# 1020.net
KiCad netlist of a schematic drawn in EAGLE
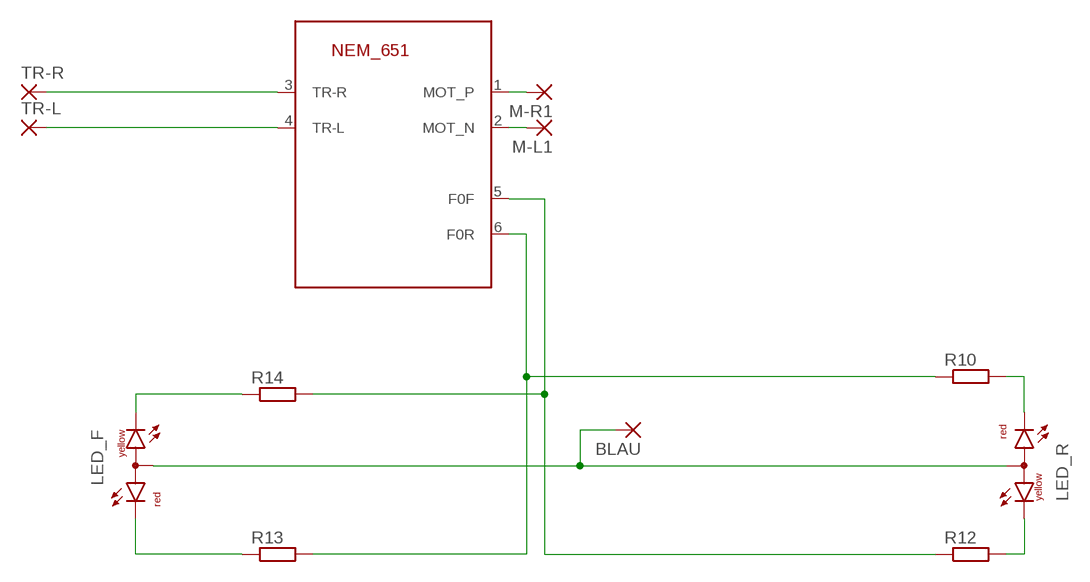
[diagram p0: schematic, sheet 1]

(export (version "E")
  (design (tool "Eeschema 10.0.6"))
  (components
    (comp (ref "651")
      (value "NEM_651-TS")
      (footprint "eagle-import:53047-06")
      (libsource (lib "eagle-import") (part "NEM_651-TS"))
    )
    (comp (ref "BLAU")
      (value "1,6/0,8")
      (footprint "eagle-import:1,6_0,8")
      (libsource (lib "eagle-import") (part "1,6/0,8"))
    )
    (comp (ref "LED_F")
      (value "DUOLED-RY-A")
      (footprint "eagle-import:DUOLED-A-5MM")
      (libsource (lib "eagle-import") (part "DUOLED-RY-A"))
    )
    (comp (ref "LED_R")
      (value "DUOLED-RY-A")
      (footprint "eagle-import:DUOLED-A-5MM")
      (libsource (lib "eagle-import") (part "DUOLED-RY-A"))
    )
    (comp (ref "M-L1")
      (value "SMD5")
      (footprint "eagle-import:SMD2,54-5,08")
      (libsource (lib "eagle-import") (part "SMD5"))
    )
    (comp (ref "M-R1")
      (value "SMD5")
      (footprint "eagle-import:SMD2,54-5,08")
      (libsource (lib "eagle-import") (part "SMD5"))
    )
    (comp (ref "R10")
      (value "R-EU_R1206")
      (footprint "eagle-import:R1206")
      (libsource (lib "eagle-import") (part "R-EU_R1206"))
    )
    (comp (ref "R12")
      (value "R-EU_R1206")
      (footprint "eagle-import:R1206")
      (libsource (lib "eagle-import") (part "R-EU_R1206"))
    )
    (comp (ref "R13")
      (value "R-EU_R1206")
      (footprint "eagle-import:R1206")
      (libsource (lib "eagle-import") (part "R-EU_R1206"))
    )
    (comp (ref "R14")
      (value "R-EU_R1206")
      (footprint "eagle-import:R1206")
      (libsource (lib "eagle-import") (part "R-EU_R1206"))
    )
    (comp (ref "TR-L")
      (value "SMD5")
      (footprint "eagle-import:SMD2,54-5,08")
      (libsource (lib "eagle-import") (part "SMD5"))
    )
    (comp (ref "TR-R")
      (value "SMD5")
      (footprint "eagle-import:SMD2,54-5,08")
      (libsource (lib "eagle-import") (part "SMD5"))
    )
  )
  (nets
    (net (code "1") (name "Net-(651-F0F)") (class "Default")
      (node (ref "651") (pin "5") (pinfunction "F0F_5") (pintype "bidirectional"))
      (node (ref "R12") (pin "1") (pinfunction "1_1") (pintype "passive"))
      (node (ref "R14") (pin "2") (pinfunction "2_2") (pintype "passive"))
    )
    (net (code "2") (name "Net-(651-F0R)") (class "Default")
      (node (ref "651") (pin "6") (pinfunction "F0R_6") (pintype "bidirectional"))
      (node (ref "R10") (pin "1") (pinfunction "1_1") (pintype "passive"))
      (node (ref "R13") (pin "2") (pinfunction "2_2") (pintype "passive"))
    )
    (net (code "3") (name "Net-(651-MOT_N)") (class "Default")
      (node (ref "651") (pin "2") (pinfunction "MOT_N_2") (pintype "bidirectional"))
      (node (ref "M-L1") (pin "1") (pinfunction "P_1") (pintype "passive"))
    )
    (net (code "4") (name "Net-(651-MOT_P)") (class "Default")
      (node (ref "651") (pin "1") (pinfunction "MOT_P_1") (pintype "bidirectional"))
      (node (ref "M-R1") (pin "1") (pinfunction "P_1") (pintype "passive"))
    )
    (net (code "5") (name "Net-(651-TR-L)") (class "Default")
      (node (ref "651") (pin "4") (pinfunction "TR-L_4") (pintype "bidirectional"))
      (node (ref "TR-L") (pin "1") (pinfunction "P_1") (pintype "passive"))
    )
    (net (code "6") (name "Net-(651-TR-R)") (class "Default")
      (node (ref "651") (pin "3") (pinfunction "TR-R_3") (pintype "bidirectional"))
      (node (ref "TR-R") (pin "1") (pinfunction "P_1") (pintype "passive"))
    )
    (net (code "7") (name "Net-(BLAU-P)") (class "Default")
      (node (ref "BLAU") (pin "1") (pinfunction "P_1") (pintype "passive"))
      (node (ref "LED_F") (pin "A") (pinfunction "A_A") (pintype "passive"))
      (node (ref "LED_R") (pin "A") (pinfunction "A_A") (pintype "passive"))
    )
    (net (code "8") (name "Net-(LED_F-CY)") (class "Default")
      (node (ref "LED_F") (pin "CX") (pinfunction "CY_CX") (pintype "passive"))
      (node (ref "R14") (pin "1") (pinfunction "1_1") (pintype "passive"))
    )
    (net (code "9") (name "Net-(LED_F-PadCR)") (class "Default")
      (node (ref "LED_F") (pin "CR") (pinfunction "CR_CR") (pintype "passive"))
      (node (ref "R13") (pin "1") (pinfunction "1_1") (pintype "passive"))
    )
    (net (code "10") (name "Net-(LED_R-CY)") (class "Default")
      (node (ref "LED_R") (pin "CX") (pinfunction "CY_CX") (pintype "passive"))
      (node (ref "R12") (pin "2") (pinfunction "2_2") (pintype "passive"))
    )
    (net (code "11") (name "Net-(LED_R-PadCR)") (class "Default")
      (node (ref "LED_R") (pin "CR") (pinfunction "CR_CR") (pintype "passive"))
      (node (ref "R10") (pin "2") (pinfunction "2_2") (pintype "passive"))
    )
  )
)
